# sd_slot.net
KiCad netlist of a schematic drawn in EAGLE
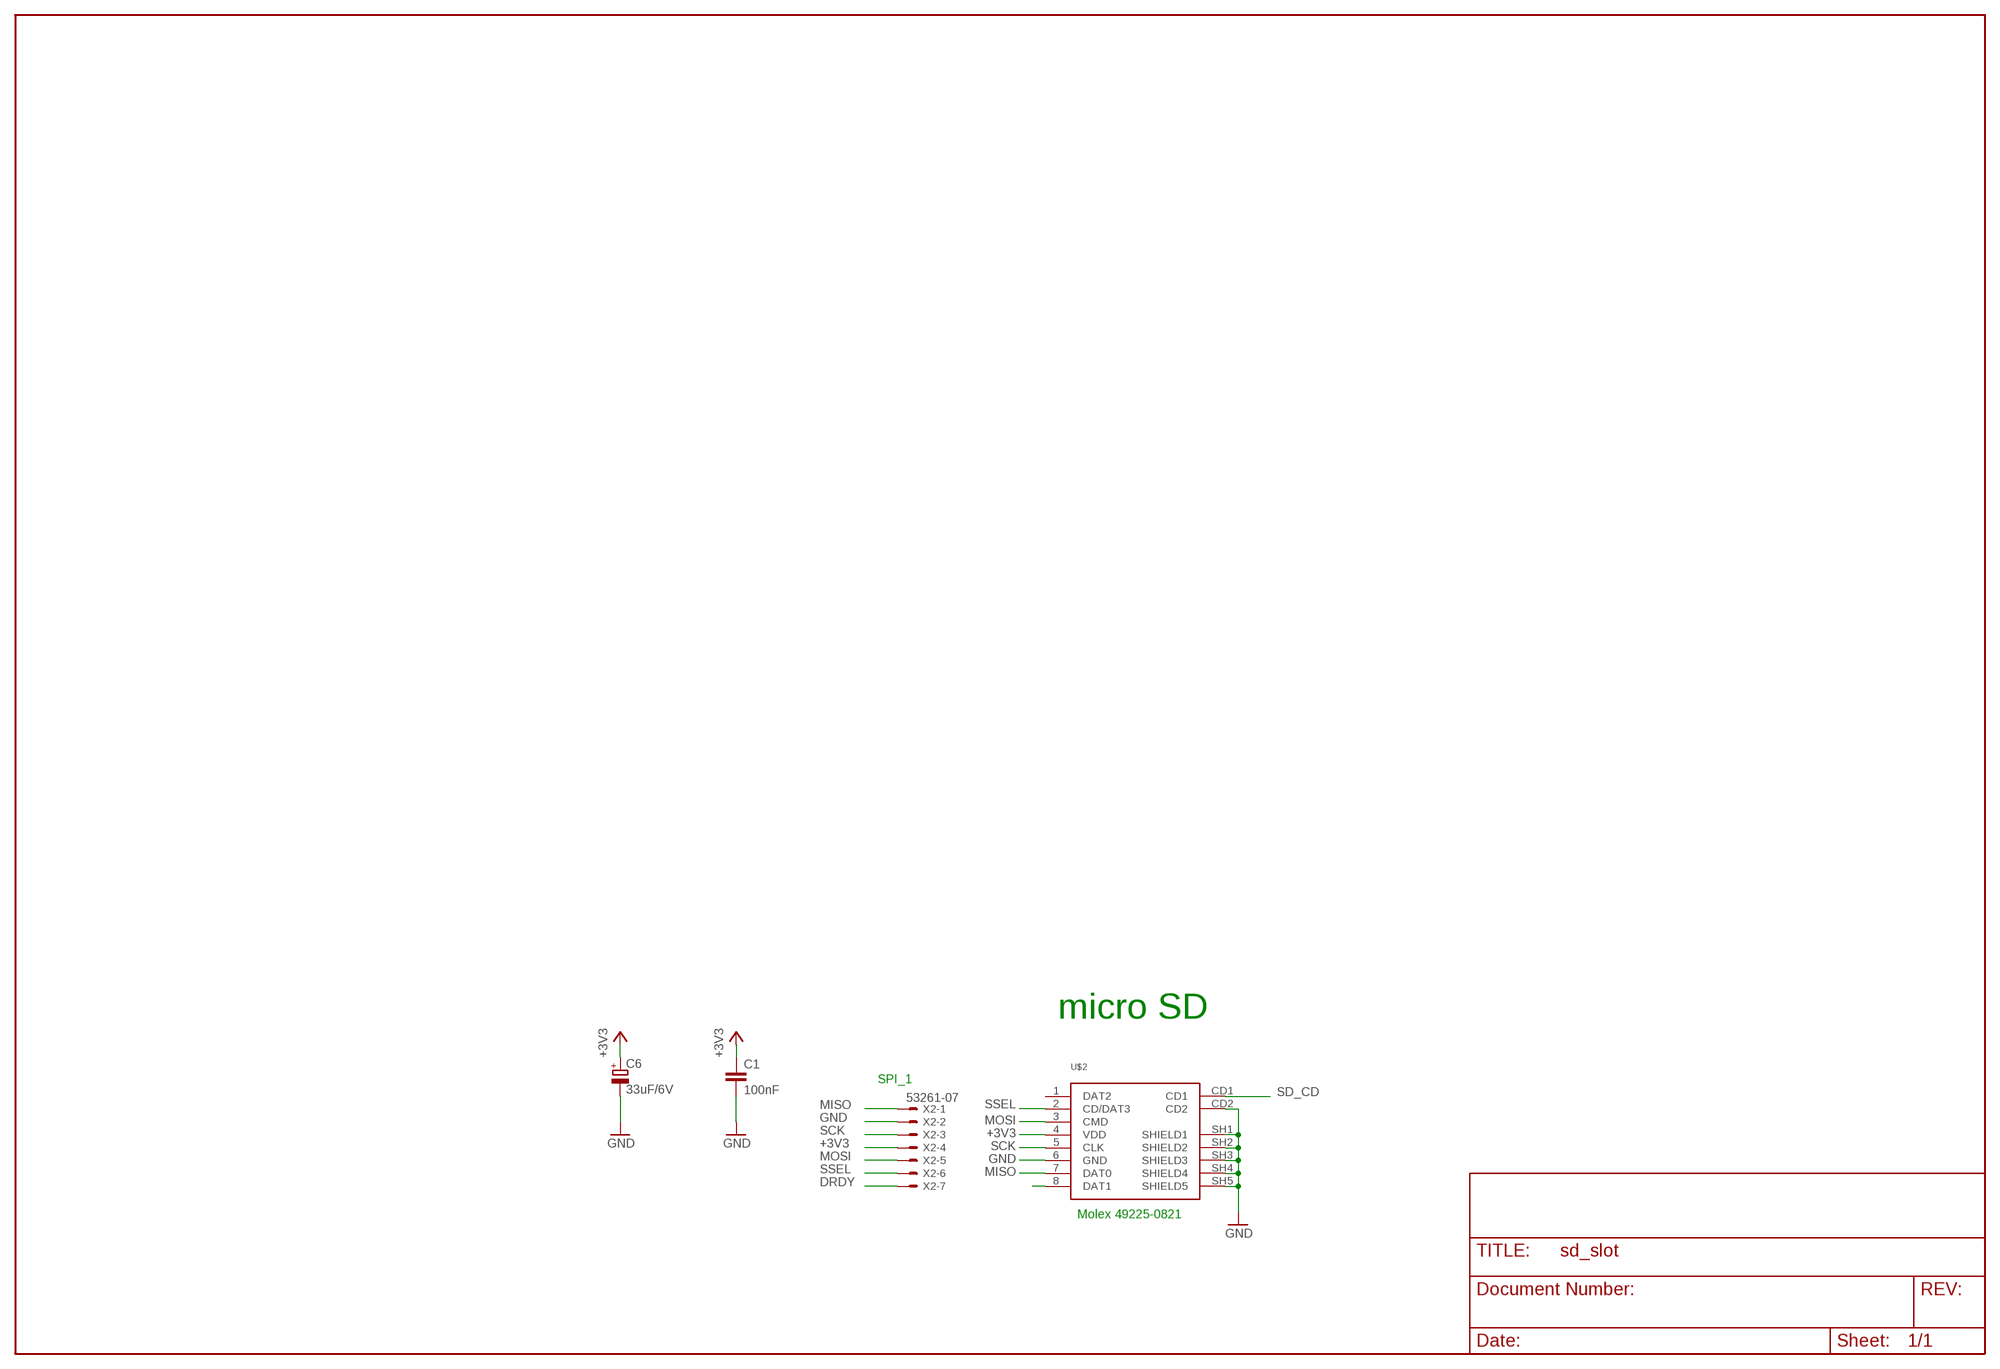
[diagram p0: schematic, sheet 1]

(export (version "E")
  (design (tool "Eeschema 10.0.6"))
  (components
    (comp (ref "C1")
      (value "100nF")
      (footprint "eagle-import:C0603")
      (libsource (lib "eagle-import") (part "C-EUC0603"))
    )
    (comp (ref "C6")
      (value "33uF/6V")
      (footprint "eagle-import:CT3216")
      (libsource (lib "eagle-import") (part "CPOL-EUCT3216"))
    )
    (comp (ref "U$2")
      (value "MICRO_SD")
      (footprint "eagle-import:SD-MOLEX-49225")
      (libsource (lib "eagle-import") (part "MICRO_SD"))
    )
    (comp (ref "X2")
      (value "53261-07")
      (footprint "eagle-import:53261-07")
      (libsource (lib "eagle-import") (part "53?-07261"))
    )
  )
  (nets
    (net (code "1") (name "+3V3") (class "Default")
      (node (ref "C1") (pin "1") (pinfunction "1_1") (pintype "passive"))
      (node (ref "C6") (pin "+") (pinfunction "+_+") (pintype "passive"))
      (node (ref "U$2") (pin "4") (pinfunction "VDD_4") (pintype "power_in"))
      (node (ref "X2") (pin "4") (pinfunction "S_4") (pintype "passive"))
    )
    (net (code "2") (name "/DRDY") (class "Default")
      (node (ref "X2") (pin "7") (pinfunction "S_7") (pintype "passive"))
    )
    (net (code "3") (name "/MISO") (class "Default")
      (node (ref "U$2") (pin "7") (pinfunction "DAT0_7") (pintype "bidirectional"))
      (node (ref "X2") (pin "1") (pinfunction "S_1") (pintype "passive"))
    )
    (net (code "4") (name "/MOSI") (class "Default")
      (node (ref "U$2") (pin "3") (pinfunction "CMD_3") (pintype "bidirectional"))
      (node (ref "X2") (pin "5") (pinfunction "S_5") (pintype "passive"))
    )
    (net (code "5") (name "/SCK") (class "Default")
      (node (ref "U$2") (pin "5") (pinfunction "CLK_5") (pintype "bidirectional"))
      (node (ref "X2") (pin "3") (pinfunction "S_3") (pintype "passive"))
    )
    (net (code "6") (name "/SD_CD") (class "Default")
      (node (ref "U$2") (pin "CD1") (pinfunction "CD1_CD1") (pintype "output"))
    )
    (net (code "7") (name "/SSEL") (class "Default")
      (node (ref "U$2") (pin "2") (pinfunction "CD/DAT3_2") (pintype "bidirectional"))
      (node (ref "X2") (pin "6") (pinfunction "S_6") (pintype "passive"))
    )
    (net (code "8") (name "GND") (class "Default")
      (node (ref "C1") (pin "2") (pinfunction "2_2") (pintype "passive"))
      (node (ref "C6") (pin "-") (pinfunction "-_-") (pintype "passive"))
      (node (ref "U$2") (pin "6") (pinfunction "GND_6") (pintype "power_in"))
      (node (ref "U$2") (pin "CD2") (pinfunction "CD2_CD2") (pintype "output"))
      (node (ref "U$2") (pin "SH1") (pinfunction "SHIELD1_SH1") (pintype "power_in"))
      (node (ref "U$2") (pin "SH2") (pinfunction "SHIELD2_SH2") (pintype "power_in"))
      (node (ref "U$2") (pin "SH3") (pinfunction "SHIELD3_SH3") (pintype "power_in"))
      (node (ref "U$2") (pin "SH4") (pinfunction "SHIELD4_SH4") (pintype "power_in"))
      (node (ref "U$2") (pin "SH5") (pinfunction "SHIELD5_SH5") (pintype "power_in"))
      (node (ref "X2") (pin "2") (pinfunction "S_2") (pintype "passive"))
    )
    (net (code "9") (name "unconnected-(U$2-DAT1-Pad8)") (class "Default")
      (node (ref "U$2") (pin "8") (pinfunction "DAT1_8") (pintype "bidirectional"))
    )
    (net (code "10") (name "unconnected-(U$2-DAT2-Pad1)") (class "Default")
      (node (ref "U$2") (pin "1") (pinfunction "DAT2_1") (pintype "bidirectional"))
    )
  )
)
